# mini-position-sensor.net
KiCad netlist of a schematic drawn in EAGLE
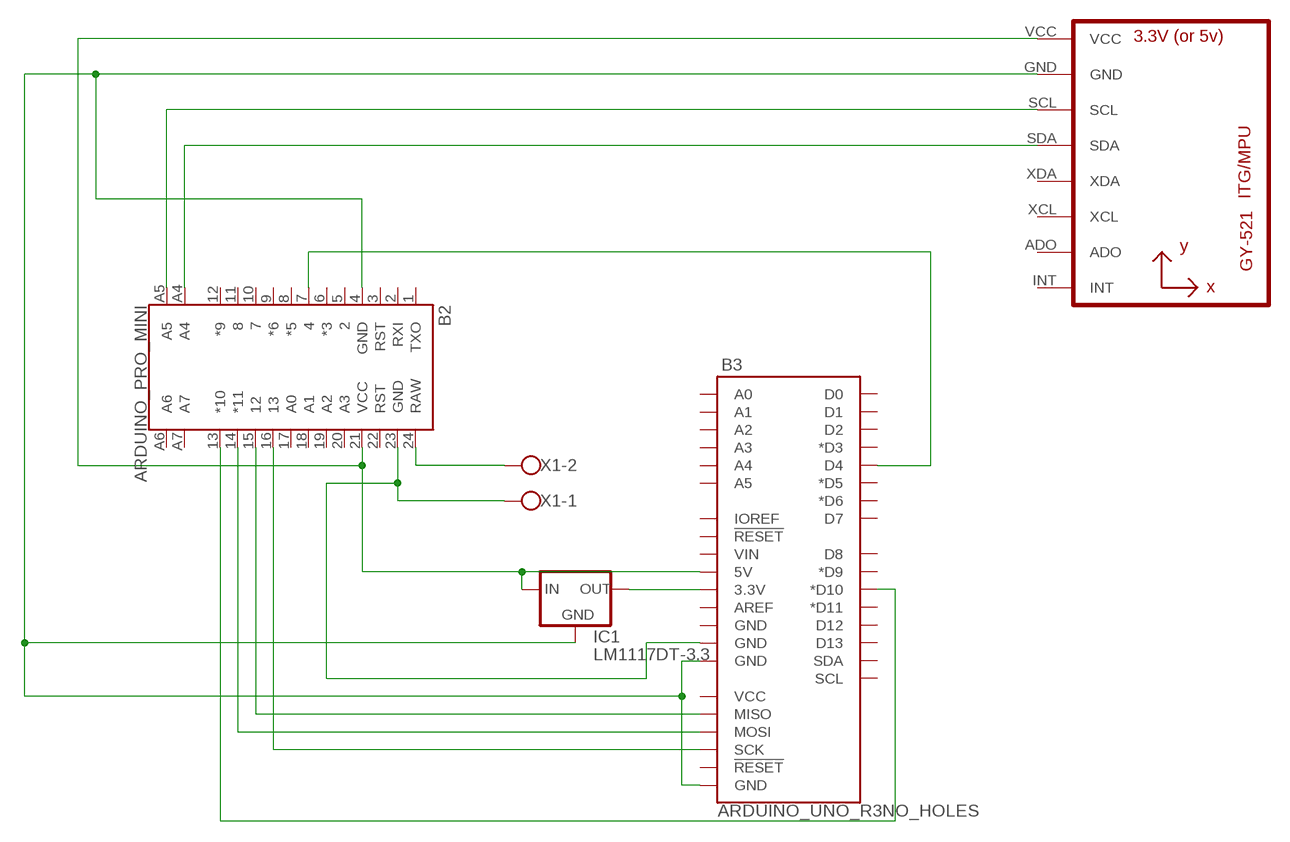
[diagram p0: schematic, sheet 1]

(export (version "E")
  (design (tool "Eeschema 10.0.6"))
  (components
    (comp (ref "B2")
      (value "ARDUINO_PRO_MINI")
      (footprint "eagle-import:ARDUINO_PRO_MINI")
      (libsource (lib "eagle-import") (part "ARDUINO_PRO_MINI"))
    )
    (comp (ref "B3")
      (value "ARDUINO_UNO_R3NO_HOLES")
      (footprint "eagle-import:ARDUINO_R3_NO_HOLES")
      (libsource (lib "eagle-import") (part "ARDUINO_UNO_R3NO_HOLES"))
    )
    (comp (ref "IC1")
      (value "LM1117DT-3.3")
      (footprint "eagle-import:TO252")
      (fields (field (name "MF") "Texas Instruments"))
      (libsource (lib "eagle-import") (part "LM1117?-DT3.3"))
    )
    (comp (ref "U1")
      (value "GY-521MPU6050")
      (footprint "eagle-import:GY-521")
      (libsource (lib "eagle-import") (part "GY-521MPU6050"))
    )
    (comp (ref "X1")
      (value "W237-102")
      (footprint "eagle-import:W237-102")
      (fields (field (name "MPN") "237-102"))
      (libsource (lib "eagle-import") (part "W237-102"))
    )
  )
  (nets
    (net (code "1") (name "Net-(B2-*10)") (class "Default")
      (node (ref "B2") (pin "13") (pinfunction "*10_13") (pintype "bidirectional"))
      (node (ref "B3") (pin "D10") (pinfunction "*D10_D10") (pintype "bidirectional"))
    )
    (net (code "2") (name "Net-(B2-*11)") (class "Default")
      (node (ref "B2") (pin "14") (pinfunction "*11_14") (pintype "bidirectional"))
      (node (ref "B3") (pin "MOSI") (pinfunction "MOSI_MOSI") (pintype "bidirectional"))
    )
    (net (code "3") (name "Net-(B2-4)") (class "Default")
      (node (ref "B2") (pin "7") (pinfunction "4_7") (pintype "bidirectional"))
      (node (ref "B3") (pin "D4") (pinfunction "D4_D4") (pintype "bidirectional"))
    )
    (net (code "4") (name "Net-(B2-12)") (class "Default")
      (node (ref "B2") (pin "15") (pinfunction "12_15") (pintype "bidirectional"))
      (node (ref "B3") (pin "MISO") (pinfunction "MISO_MISO") (pintype "bidirectional"))
    )
    (net (code "5") (name "Net-(B2-13)") (class "Default")
      (node (ref "B2") (pin "16") (pinfunction "13_16") (pintype "bidirectional"))
      (node (ref "B3") (pin "SCK") (pinfunction "SCK_SCK") (pintype "bidirectional"))
    )
    (net (code "6") (name "Net-(B2-PadA4)") (class "Default")
      (node (ref "B2") (pin "A4") (pinfunction "A4_A4") (pintype "bidirectional"))
      (node (ref "U1") (pin "SDA") (pinfunction "SDA_SDA") (pintype "bidirectional"))
    )
    (net (code "7") (name "Net-(B2-PadA5)") (class "Default")
      (node (ref "B2") (pin "A5") (pinfunction "A5_A5") (pintype "bidirectional"))
      (node (ref "U1") (pin "SCL") (pinfunction "SCL_SCL") (pintype "bidirectional"))
    )
    (net (code "8") (name "Net-(B2-RAW)") (class "Default")
      (node (ref "B2") (pin "24") (pinfunction "RAW_24") (pintype "power_in"))
      (node (ref "X1") (pin "2") (pinfunction "KL_2") (pintype "passive"))
    )
    (net (code "9") (name "Net-(B2-VCC)") (class "Default")
      (node (ref "B2") (pin "21") (pinfunction "VCC_21") (pintype "power_in"))
      (node (ref "B3") (pin "5V") (pinfunction "5V_5V") (pintype "bidirectional"))
      (node (ref "IC1") (pin "2") (pinfunction "IN_2") (pintype "input"))
      (node (ref "U1") (pin "VCC") (pinfunction "VCC_VCC") (pintype "bidirectional"))
    )
    (net (code "10") (name "Net-(IC1-GND)") (class "Default")
      (node (ref "B2") (pin "4") (pinfunction "GND_4") (pintype "power_in"))
      (node (ref "B3") (pin "GND@1") (pinfunction "GND_GND@1") (pintype "bidirectional"))
      (node (ref "B3") (pin "GND@2") (pinfunction "GND_GND@2") (pintype "bidirectional"))
      (node (ref "IC1") (pin "1") (pinfunction "GND_1") (pintype "input"))
      (node (ref "U1") (pin "GND") (pinfunction "GND_GND") (pintype "bidirectional"))
    )
    (net (code "11") (name "Net-(IC1-OUT)") (class "Default")
      (node (ref "B3") (pin "3.3V") (pinfunction "3.3V_3.3V") (pintype "bidirectional"))
      (node (ref "IC1") (pin "3") (pinfunction "OUT_3") (pintype "passive"))
    )
    (net (code "12") (name "Net-(X1A-KL)") (class "Default")
      (node (ref "B2") (pin "23") (pinfunction "GND_23") (pintype "power_in"))
      (node (ref "B3") (pin "GND@3") (pinfunction "GND_GND@3") (pintype "bidirectional"))
      (node (ref "X1") (pin "1") (pinfunction "KL_1") (pintype "passive"))
    )
    (net (code "13") (name "unconnected-(B2-*3-Pad6)") (class "Default")
      (node (ref "B2") (pin "6") (pinfunction "*3_6") (pintype "bidirectional"))
    )
    (net (code "14") (name "unconnected-(B2-*5-Pad8)") (class "Default")
      (node (ref "B2") (pin "8") (pinfunction "*5_8") (pintype "bidirectional"))
    )
    (net (code "15") (name "unconnected-(B2-*6-Pad9)") (class "Default")
      (node (ref "B2") (pin "9") (pinfunction "*6_9") (pintype "bidirectional"))
    )
    (net (code "16") (name "unconnected-(B2-*9-Pad12)") (class "Default")
      (node (ref "B2") (pin "12") (pinfunction "*9_12") (pintype "bidirectional"))
    )
    (net (code "17") (name "unconnected-(B2-2-Pad5)") (class "Default")
      (node (ref "B2") (pin "5") (pinfunction "2_5") (pintype "bidirectional"))
    )
    (net (code "18") (name "unconnected-(B2-7-Pad10)") (class "Default")
      (node (ref "B2") (pin "10") (pinfunction "7_10") (pintype "bidirectional"))
    )
    (net (code "19") (name "unconnected-(B2-8-Pad11)") (class "Default")
      (node (ref "B2") (pin "11") (pinfunction "8_11") (pintype "bidirectional"))
    )
    (net (code "20") (name "unconnected-(B2-A0-Pad17)") (class "Default")
      (node (ref "B2") (pin "17") (pinfunction "A0_17") (pintype "bidirectional"))
    )
    (net (code "21") (name "unconnected-(B2-A1-Pad18)") (class "Default")
      (node (ref "B2") (pin "18") (pinfunction "A1_18") (pintype "bidirectional"))
    )
    (net (code "22") (name "unconnected-(B2-A2-Pad19)") (class "Default")
      (node (ref "B2") (pin "19") (pinfunction "A2_19") (pintype "bidirectional"))
    )
    (net (code "23") (name "unconnected-(B2-A3-Pad20)") (class "Default")
      (node (ref "B2") (pin "20") (pinfunction "A3_20") (pintype "bidirectional"))
    )
    (net (code "24") (name "unconnected-(B2-PadA6)") (class "Default")
      (node (ref "B2") (pin "A6") (pinfunction "A6_A6") (pintype "bidirectional"))
    )
    (net (code "25") (name "unconnected-(B2-PadA7)") (class "Default")
      (node (ref "B2") (pin "A7") (pinfunction "A7_A7") (pintype "bidirectional"))
    )
    (net (code "26") (name "unconnected-(B2-RST-Pad3)") (class "Default")
      (node (ref "B2") (pin "3") (pinfunction "RST_3") (pintype "bidirectional"))
    )
    (net (code "27") (name "unconnected-(B2-RST-Pad22)") (class "Default")
      (node (ref "B2") (pin "22") (pinfunction "RST_22") (pintype "bidirectional"))
    )
    (net (code "28") (name "unconnected-(B2-RXI-Pad2)") (class "Default")
      (node (ref "B2") (pin "2") (pinfunction "RXI_2") (pintype "bidirectional"))
    )
    (net (code "29") (name "unconnected-(B2-TXO-Pad1)") (class "Default")
      (node (ref "B2") (pin "1") (pinfunction "TXO_1") (pintype "bidirectional"))
    )
    (net (code "30") (name "unconnected-(B3-*D3-PadD3)") (class "Default")
      (node (ref "B3") (pin "D3") (pinfunction "*D3_D3") (pintype "bidirectional"))
    )
    (net (code "31") (name "unconnected-(B3-*D5-PadD5)") (class "Default")
      (node (ref "B3") (pin "D5") (pinfunction "*D5_D5") (pintype "bidirectional"))
    )
    (net (code "32") (name "unconnected-(B3-*D6-PadD6)") (class "Default")
      (node (ref "B3") (pin "D6") (pinfunction "*D6_D6") (pintype "bidirectional"))
    )
    (net (code "33") (name "unconnected-(B3-*D9-PadD9)") (class "Default")
      (node (ref "B3") (pin "D9") (pinfunction "*D9_D9") (pintype "bidirectional"))
    )
    (net (code "34") (name "unconnected-(B3-*D11-PadD11)") (class "Default")
      (node (ref "B3") (pin "D11") (pinfunction "*D11_D11") (pintype "bidirectional"))
    )
    (net (code "35") (name "unconnected-(B3-GND-PadGND@4)") (class "Default")
      (node (ref "B3") (pin "GND@4") (pinfunction "GND_GND@4") (pintype "bidirectional"))
    )
    (net (code "36") (name "unconnected-(B3-PadA0)") (class "Default")
      (node (ref "B3") (pin "A0") (pinfunction "A0_A0") (pintype "bidirectional"))
    )
    (net (code "37") (name "unconnected-(B3-PadA1)") (class "Default")
      (node (ref "B3") (pin "A1") (pinfunction "A1_A1") (pintype "bidirectional"))
    )
    (net (code "38") (name "unconnected-(B3-PadA2)") (class "Default")
      (node (ref "B3") (pin "A2") (pinfunction "A2_A2") (pintype "bidirectional"))
    )
    (net (code "39") (name "unconnected-(B3-PadA3)") (class "Default")
      (node (ref "B3") (pin "A3") (pinfunction "A3_A3") (pintype "bidirectional"))
    )
    (net (code "40") (name "unconnected-(B3-PadA4)") (class "Default")
      (node (ref "B3") (pin "A4") (pinfunction "A4_A4") (pintype "bidirectional"))
    )
    (net (code "41") (name "unconnected-(B3-PadA5)") (class "Default")
      (node (ref "B3") (pin "A5") (pinfunction "A5_A5") (pintype "bidirectional"))
    )
    (net (code "42") (name "unconnected-(B3-PadAREF)") (class "Default")
      (node (ref "B3") (pin "AREF") (pinfunction "AREF_AREF") (pintype "bidirectional"))
    )
    (net (code "43") (name "unconnected-(B3-PadD0)") (class "Default")
      (node (ref "B3") (pin "D0") (pinfunction "D0_D0") (pintype "bidirectional"))
    )
    (net (code "44") (name "unconnected-(B3-PadD1)") (class "Default")
      (node (ref "B3") (pin "D1") (pinfunction "D1_D1") (pintype "bidirectional"))
    )
    (net (code "45") (name "unconnected-(B3-PadD2)") (class "Default")
      (node (ref "B3") (pin "D2") (pinfunction "D2_D2") (pintype "bidirectional"))
    )
    (net (code "46") (name "unconnected-(B3-PadD7)") (class "Default")
      (node (ref "B3") (pin "D7") (pinfunction "D7_D7") (pintype "bidirectional"))
    )
    (net (code "47") (name "unconnected-(B3-PadD8)") (class "Default")
      (node (ref "B3") (pin "D8") (pinfunction "D8_D8") (pintype "bidirectional"))
    )
    (net (code "48") (name "unconnected-(B3-PadD12)") (class "Default")
      (node (ref "B3") (pin "D12") (pinfunction "D12_D12") (pintype "bidirectional"))
    )
    (net (code "49") (name "unconnected-(B3-PadD13)") (class "Default")
      (node (ref "B3") (pin "D13") (pinfunction "D13_D13") (pintype "bidirectional"))
    )
    (net (code "50") (name "unconnected-(B3-PadIOREF)") (class "Default")
      (node (ref "B3") (pin "IOREF") (pinfunction "IOREF_IOREF") (pintype "bidirectional"))
    )
    (net (code "51") (name "unconnected-(B3-PadSCL)") (class "Default")
      (node (ref "B3") (pin "SCL") (pinfunction "SCL_SCL") (pintype "bidirectional"))
    )
    (net (code "52") (name "unconnected-(B3-PadSDA)") (class "Default")
      (node (ref "B3") (pin "SDA") (pinfunction "SDA_SDA") (pintype "bidirectional"))
    )
    (net (code "53") (name "unconnected-(B3-PadVCC)") (class "Default")
      (node (ref "B3") (pin "VCC") (pinfunction "VCC_VCC") (pintype "bidirectional"))
    )
    (net (code "54") (name "unconnected-(B3-PadVIN)") (class "Default")
      (node (ref "B3") (pin "VIN") (pinfunction "VIN_VIN") (pintype "bidirectional"))
    )
    (net (code "55") (name "unconnected-(B3-~{RESET}-PadRESET@1)") (class "Default")
      (node (ref "B3") (pin "RESET@1") (pinfunction "~{RESET}_RESET@1") (pintype "bidirectional"))
    )
    (net (code "56") (name "unconnected-(B3-~{RESET}-PadRESET@2)") (class "Default")
      (node (ref "B3") (pin "RESET@2") (pinfunction "~{RESET}_RESET@2") (pintype "bidirectional"))
    )
    (net (code "57") (name "unconnected-(U1-PadADO)") (class "Default")
      (node (ref "U1") (pin "ADO") (pinfunction "ADO_ADO") (pintype "bidirectional"))
    )
    (net (code "58") (name "unconnected-(U1-PadINT)") (class "Default")
      (node (ref "U1") (pin "INT") (pinfunction "INT_INT") (pintype "bidirectional"))
    )
    (net (code "59") (name "unconnected-(U1-PadXCL)") (class "Default")
      (node (ref "U1") (pin "XCL") (pinfunction "XCL_XCL") (pintype "bidirectional"))
    )
    (net (code "60") (name "unconnected-(U1-PadXDA)") (class "Default")
      (node (ref "U1") (pin "XDA") (pinfunction "XDA_XDA") (pintype "bidirectional"))
    )
  )
)
